# ShoulderDriver.net
KiCad netlist of a schematic drawn in Altium Designer
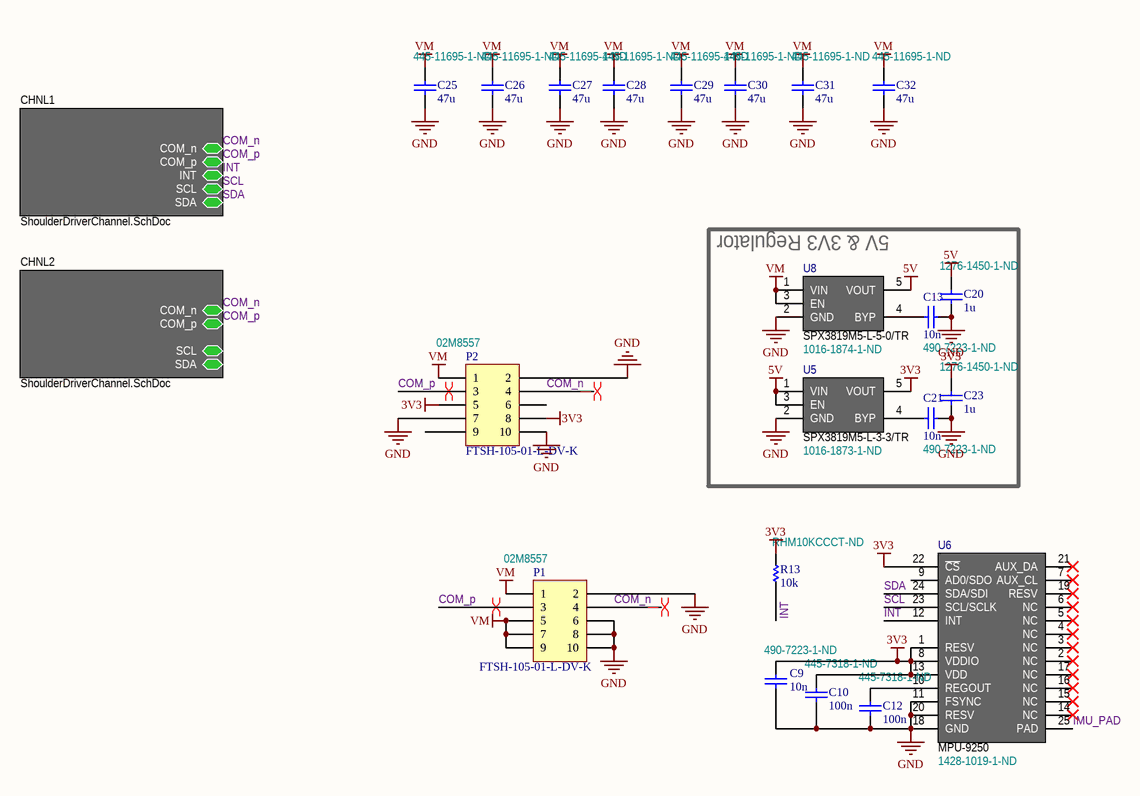
[diagram p0: ShoulderDriver.SchDoc]

(export (version "E")
  (design (tool "Eeschema 10.0.6"))
  (components
    (comp (ref "C9")
      (value "10n")
      (footprint "CAPC0603N")
      (description "Capacitor (Semiconductor SIM Model)")
      (fields
        (field (name "SUPPLIER PART NUMBER 1") "490-7223-1-ND")
        (field (name "PUBLISHER") "Altium Limited")
      )
      (libsource (lib "Miscellaneous Devices") (part "Cap Semi"))
    )
    (comp (ref "C10")
      (value "100n")
      (footprint "CAPC0603N")
      (description "Capacitor (Semiconductor SIM Model)")
      (fields
        (field (name "SUPPLIER PART NUMBER 1") "445-7318-1-ND")
        (field (name "PUBLISHER") "Altium Limited")
      )
      (libsource (lib "Miscellaneous Devices") (part "Cap Semi"))
    )
    (comp (ref "C12")
      (value "100n")
      (footprint "CAPC0603N")
      (description "Capacitor (Semiconductor SIM Model)")
      (fields
        (field (name "SUPPLIER PART NUMBER 1") "445-7318-1-ND")
        (field (name "PUBLISHER") "Altium Limited")
      )
      (libsource (lib "Miscellaneous Devices") (part "Cap Semi"))
    )
    (comp (ref "C13")
      (value "10n")
      (footprint "CAPC0603N")
      (description "Capacitor (Semiconductor SIM Model)")
      (fields
        (field (name "SUPPLIER PART NUMBER 1") "490-7223-1-ND")
        (field (name "PUBLISHER") "Altium Limited")
      )
      (libsource (lib "Miscellaneous Devices") (part "Cap Semi"))
    )
    (comp (ref "C20")
      (value "1u")
      (footprint "CAPC1005N")
      (description "Capacitor (Semiconductor SIM Model)")
      (fields
        (field (name "SUPPLIER PART NUMBER 1") "1276-1450-1-ND")
        (field (name "PUBLISHER") "Altium Limited")
      )
      (libsource (lib "Miscellaneous Devices") (part "Cap Semi"))
    )
    (comp (ref "C21")
      (value "10n")
      (footprint "CAPC0603N")
      (description "Capacitor (Semiconductor SIM Model)")
      (fields
        (field (name "SUPPLIER PART NUMBER 1") "490-7223-1-ND")
        (field (name "PUBLISHER") "Altium Limited")
      )
      (libsource (lib "Miscellaneous Devices") (part "Cap Semi"))
    )
    (comp (ref "C23")
      (value "1u")
      (footprint "CAPC1005N")
      (description "Capacitor (Semiconductor SIM Model)")
      (fields
        (field (name "SUPPLIER PART NUMBER 1") "1276-1450-1-ND")
        (field (name "PUBLISHER") "Altium Limited")
      )
      (libsource (lib "Miscellaneous Devices") (part "Cap Semi"))
    )
    (comp (ref "C25")
      (value "47u")
      (footprint "CAPC3216N")
      (description "Capacitor (Semiconductor SIM Model)")
      (fields
        (field (name "SUPPLIER PART NUMBER 1") "445-11695-1-ND")
        (field (name "PUBLISHER") "Altium Limited")
      )
      (libsource (lib "Miscellaneous Devices") (part "Cap Semi"))
    )
    (comp (ref "C26")
      (value "47u")
      (footprint "CAPC3216N")
      (description "Capacitor (Semiconductor SIM Model)")
      (fields
        (field (name "SUPPLIER PART NUMBER 1") "445-11695-1-ND")
        (field (name "PUBLISHER") "Altium Limited")
      )
      (libsource (lib "Miscellaneous Devices") (part "Cap Semi"))
    )
    (comp (ref "C27")
      (value "47u")
      (footprint "CAPC3216N")
      (description "Capacitor (Semiconductor SIM Model)")
      (fields
        (field (name "SUPPLIER PART NUMBER 1") "445-11695-1-ND")
        (field (name "PUBLISHER") "Altium Limited")
      )
      (libsource (lib "Miscellaneous Devices") (part "Cap Semi"))
    )
    (comp (ref "C28")
      (value "47u")
      (footprint "CAPC3216N")
      (description "Capacitor (Semiconductor SIM Model)")
      (fields
        (field (name "SUPPLIER PART NUMBER 1") "445-11695-1-ND")
        (field (name "PUBLISHER") "Altium Limited")
      )
      (libsource (lib "Miscellaneous Devices") (part "Cap Semi"))
    )
    (comp (ref "C29")
      (value "47u")
      (footprint "CAPC3216N")
      (description "Capacitor (Semiconductor SIM Model)")
      (fields
        (field (name "SUPPLIER PART NUMBER 1") "445-11695-1-ND")
        (field (name "PUBLISHER") "Altium Limited")
      )
      (libsource (lib "Miscellaneous Devices") (part "Cap Semi"))
    )
    (comp (ref "C30")
      (value "47u")
      (footprint "CAPC3216N")
      (description "Capacitor (Semiconductor SIM Model)")
      (fields
        (field (name "SUPPLIER PART NUMBER 1") "445-11695-1-ND")
        (field (name "PUBLISHER") "Altium Limited")
      )
      (libsource (lib "Miscellaneous Devices") (part "Cap Semi"))
    )
    (comp (ref "C31")
      (value "47u")
      (footprint "CAPC3216N")
      (description "Capacitor (Semiconductor SIM Model)")
      (fields
        (field (name "SUPPLIER PART NUMBER 1") "445-11695-1-ND")
        (field (name "PUBLISHER") "Altium Limited")
      )
      (libsource (lib "Miscellaneous Devices") (part "Cap Semi"))
    )
    (comp (ref "C32")
      (value "47u")
      (footprint "CAPC3216N")
      (description "Capacitor (Semiconductor SIM Model)")
      (fields
        (field (name "SUPPLIER PART NUMBER 1") "445-11695-1-ND")
        (field (name "PUBLISHER") "Altium Limited")
      )
      (libsource (lib "Miscellaneous Devices") (part "Cap Semi"))
    )
    (comp (ref "P1")
      (value "FTSH-105-01-L-DV-K")
      (footprint "FTSH-105-01-L-DV-K")
      (description "Header, 5-Pin, Dual row")
      (fields (field (name "SUPPLIER PART NUMBER 1") "02M8557") (field (name "PUBLISHER") "Altium Limited"))
      (libsource (lib "Miscellaneous Connectors") (part "MHDR2X5"))
    )
    (comp (ref "P2")
      (value "FTSH-105-01-L-DV-K")
      (footprint "FTSH-105-01-L-DV-K")
      (description "Header, 5-Pin, Dual row")
      (fields (field (name "SUPPLIER PART NUMBER 1") "02M8557") (field (name "PUBLISHER") "Altium Limited"))
      (libsource (lib "Miscellaneous Connectors") (part "MHDR2X5"))
    )
    (comp (ref "R13")
      (value "10k")
      (footprint "RESC0603N")
      (description "Semiconductor Resistor")
      (fields
        (field (name "SUPPLIER PART NUMBER 1") "RHM10KCCCT-ND")
        (field (name "PUBLISHER") "Altium Limited")
      )
      (libsource (lib "Miscellaneous Devices") (part "Res Semi"))
    )
    (comp (ref "U5")
      (value "SPX3819M5-L-3-3/TR")
      (footprint "SOT23-5AN")
      (description "IC REG LDO 3.3V 0.5A SOT23-5")
      (fields
        (field (name "MANUFACTURER") "Exar Corporation")
        (field (name "SUPPLIER PART NUMBER 1") "1016-1873-1-ND")
      )
      (libsource (lib "Exar LDO Regulator") (part "SPX3819M5-L-3-3/TR"))
    )
    (comp (ref "U6")
      (value "MPU-9250")
      (footprint "QFN40P300X300X105_HS-25N")
      (description "GYRO/ACCEL/COMPASS/9-AXIS")
      (fields
        (field (name "MANUFACTURER") "InvenSense")
        (field (name "SUPPLIER PART NUMBER 1") "1428-1019-1-ND")
      )
      (libsource (lib "Invensense MPU") (part "MPU-9250"))
    )
    (comp (ref "U8")
      (value "SPX3819M5-L-5-0/TR")
      (footprint "SOT23-5AN")
      (description "IC REG LDO 5V 0.5A SOT23-5")
      (fields
        (field (name "MANUFACTURER") "Exar Corporation")
        (field (name "SUPPLIER PART NUMBER 1") "1016-1874-1-ND")
      )
      (libsource (lib "Exar LDO Regulator") (part "SPX3819M5-L-5-0/TR"))
    )
  )
  (nets
    (net (code "1") (name "/COM_n") (class "Default")
      (node (ref "P1") (pin "4") (pinfunction "4_4") (pintype "passive"))
      (node (ref "P2") (pin "4") (pinfunction "4_4") (pintype "passive"))
    )
    (net (code "2") (name "/COM_p") (class "Default")
      (node (ref "P1") (pin "3") (pinfunction "3_3") (pintype "passive"))
      (node (ref "P2") (pin "3") (pinfunction "3_3") (pintype "passive"))
    )
    (net (code "3") (name "/IMU_PAD") (class "Default")
      (node (ref "U6") (pin "25") (pinfunction "PAD_25") (pintype "power_in"))
    )
    (net (code "4") (name "/INT") (class "Default")
      (node (ref "R13") (pin "1") (pinfunction "1_1") (pintype "passive"))
      (node (ref "U6") (pin "12") (pinfunction "INT_12") (pintype "power_in"))
    )
    (net (code "5") (name "/SCL") (class "Default")
      (node (ref "U6") (pin "23") (pinfunction "SCL/SCLK_23") (pintype "power_in"))
    )
    (net (code "7") (name "/SDA") (class "Default")
      (node (ref "U6") (pin "24") (pinfunction "SDA/SDI_24") (pintype "power_in"))
    )
    (net (code "9") (name "3V3") (class "Default")
      (node (ref "C10") (pin "2") (pinfunction "2_2") (pintype "passive"))
      (node (ref "C23") (pin "2") (pinfunction "2_2") (pintype "passive"))
      (node (ref "C9") (pin "2") (pinfunction "2_2") (pintype "passive"))
      (node (ref "P2") (pin "5") (pinfunction "5_5") (pintype "passive"))
      (node (ref "P2") (pin "8") (pinfunction "8_8") (pintype "passive"))
      (node (ref "R13") (pin "2") (pinfunction "2_2") (pintype "passive"))
      (node (ref "U5") (pin "5") (pinfunction "VOUT_5") (pintype "power_in"))
      (node (ref "U6") (pin "1") (pinfunction "RESV_1") (pintype "power_in"))
      (node (ref "U6") (pin "13") (pinfunction "VDD_13") (pintype "power_in"))
      (node (ref "U6") (pin "22") (pinfunction "~{CS}_22") (pintype "power_in"))
      (node (ref "U6") (pin "8") (pinfunction "VDDIO_8") (pintype "power_in"))
    )
    (net (code "10") (name "5V") (class "Default")
      (node (ref "C20") (pin "2") (pinfunction "2_2") (pintype "passive"))
      (node (ref "U5") (pin "1") (pinfunction "VIN_1") (pintype "power_in"))
      (node (ref "U5") (pin "3") (pinfunction "EN_3") (pintype "power_in"))
      (node (ref "U8") (pin "5") (pinfunction "VOUT_5") (pintype "power_in"))
    )
    (net (code "11") (name "GND") (class "Default")
      (node (ref "C10") (pin "1") (pinfunction "1_1") (pintype "passive"))
      (node (ref "C12") (pin "1") (pinfunction "1_1") (pintype "passive"))
      (node (ref "C13") (pin "1") (pinfunction "1_1") (pintype "passive"))
      (node (ref "C20") (pin "1") (pinfunction "1_1") (pintype "passive"))
      (node (ref "C21") (pin "1") (pinfunction "1_1") (pintype "passive"))
      (node (ref "C23") (pin "1") (pinfunction "1_1") (pintype "passive"))
      (node (ref "C25") (pin "1") (pinfunction "1_1") (pintype "passive"))
      (node (ref "C26") (pin "1") (pinfunction "1_1") (pintype "passive"))
      (node (ref "C27") (pin "1") (pinfunction "1_1") (pintype "passive"))
      (node (ref "C28") (pin "1") (pinfunction "1_1") (pintype "passive"))
      (node (ref "C29") (pin "1") (pinfunction "1_1") (pintype "passive"))
      (node (ref "C30") (pin "1") (pinfunction "1_1") (pintype "passive"))
      (node (ref "C31") (pin "1") (pinfunction "1_1") (pintype "passive"))
      (node (ref "C32") (pin "1") (pinfunction "1_1") (pintype "passive"))
      (node (ref "C9") (pin "1") (pinfunction "1_1") (pintype "passive"))
      (node (ref "P1") (pin "10") (pinfunction "10_10") (pintype "passive"))
      (node (ref "P1") (pin "2") (pinfunction "2_2") (pintype "passive"))
      (node (ref "P1") (pin "6") (pinfunction "6_6") (pintype "passive"))
      (node (ref "P1") (pin "8") (pinfunction "8_8") (pintype "passive"))
      (node (ref "P2") (pin "10") (pinfunction "10_10") (pintype "passive"))
      (node (ref "P2") (pin "2") (pinfunction "2_2") (pintype "passive"))
      (node (ref "P2") (pin "7") (pinfunction "7_7") (pintype "passive"))
      (node (ref "U5") (pin "2") (pinfunction "GND_2") (pintype "power_in"))
      (node (ref "U6") (pin "11") (pinfunction "FSYNC_11") (pintype "power_in"))
      (node (ref "U6") (pin "18") (pinfunction "GND_18") (pintype "power_in"))
      (node (ref "U6") (pin "20") (pinfunction "RESV_20") (pintype "power_in"))
      (node (ref "U8") (pin "2") (pinfunction "GND_2") (pintype "power_in"))
    )
    (net (code "12") (name "Net-(U5-BYP)") (class "Default")
      (node (ref "C21") (pin "2") (pinfunction "2_2") (pintype "passive"))
      (node (ref "U5") (pin "4") (pinfunction "BYP_4") (pintype "power_in"))
    )
    (net (code "13") (name "Net-(U6-REGOUT)") (class "Default")
      (node (ref "C12") (pin "2") (pinfunction "2_2") (pintype "passive"))
      (node (ref "U6") (pin "10") (pinfunction "REGOUT_10") (pintype "power_in"))
    )
    (net (code "14") (name "Net-(U8-BYP)") (class "Default")
      (node (ref "C13") (pin "2") (pinfunction "2_2") (pintype "passive"))
      (node (ref "U8") (pin "4") (pinfunction "BYP_4") (pintype "power_in"))
    )
    (net (code "15") (name "VM") (class "Default")
      (node (ref "C25") (pin "2") (pinfunction "2_2") (pintype "passive"))
      (node (ref "C26") (pin "2") (pinfunction "2_2") (pintype "passive"))
      (node (ref "C27") (pin "2") (pinfunction "2_2") (pintype "passive"))
      (node (ref "C28") (pin "2") (pinfunction "2_2") (pintype "passive"))
      (node (ref "C29") (pin "2") (pinfunction "2_2") (pintype "passive"))
      (node (ref "C30") (pin "2") (pinfunction "2_2") (pintype "passive"))
      (node (ref "C31") (pin "2") (pinfunction "2_2") (pintype "passive"))
      (node (ref "C32") (pin "2") (pinfunction "2_2") (pintype "passive"))
      (node (ref "P1") (pin "1") (pinfunction "1_1") (pintype "passive"))
      (node (ref "P1") (pin "5") (pinfunction "5_5") (pintype "passive"))
      (node (ref "P1") (pin "7") (pinfunction "7_7") (pintype "passive"))
      (node (ref "P1") (pin "9") (pinfunction "9_9") (pintype "passive"))
      (node (ref "P2") (pin "1") (pinfunction "1_1") (pintype "passive"))
      (node (ref "U8") (pin "1") (pinfunction "VIN_1") (pintype "power_in"))
      (node (ref "U8") (pin "3") (pinfunction "EN_3") (pintype "power_in"))
    )
    (net (code "16") (name "unconnected-(P2-Pad6)") (class "Default")
      (node (ref "P2") (pin "6") (pinfunction "6_6") (pintype "passive"))
    )
    (net (code "17") (name "unconnected-(P2-Pad9)") (class "Default")
      (node (ref "P2") (pin "9") (pinfunction "9_9") (pintype "passive"))
    )
    (net (code "18") (name "unconnected-(U6-AD0{slash}SDO-Pad9)") (class "Default")
      (node (ref "U6") (pin "9") (pinfunction "AD0/SDO_9") (pintype "power_in"))
    )
    (net (code "19") (name "unconnected-(U6-AUX_CL-Pad7)") (class "Default")
      (node (ref "U6") (pin "7") (pinfunction "AUX_CL_7") (pintype "power_in+no_connect"))
    )
    (net (code "20") (name "unconnected-(U6-AUX_DA-Pad21)") (class "Default")
      (node (ref "U6") (pin "21") (pinfunction "AUX_DA_21") (pintype "power_in+no_connect"))
    )
    (net (code "21") (name "unconnected-(U6-NC-Pad2)") (class "Default")
      (node (ref "U6") (pin "2") (pinfunction "NC_2") (pintype "power_in+no_connect"))
    )
    (net (code "22") (name "unconnected-(U6-NC-Pad3)") (class "Default")
      (node (ref "U6") (pin "3") (pinfunction "NC_3") (pintype "power_in+no_connect"))
    )
    (net (code "23") (name "unconnected-(U6-NC-Pad4)") (class "Default")
      (node (ref "U6") (pin "4") (pinfunction "NC_4") (pintype "power_in+no_connect"))
    )
    (net (code "24") (name "unconnected-(U6-NC-Pad5)") (class "Default")
      (node (ref "U6") (pin "5") (pinfunction "NC_5") (pintype "power_in+no_connect"))
    )
    (net (code "25") (name "unconnected-(U6-NC-Pad6)") (class "Default")
      (node (ref "U6") (pin "6") (pinfunction "NC_6") (pintype "power_in+no_connect"))
    )
    (net (code "26") (name "unconnected-(U6-NC-Pad14)") (class "Default")
      (node (ref "U6") (pin "14") (pinfunction "NC_14") (pintype "power_in+no_connect"))
    )
    (net (code "27") (name "unconnected-(U6-NC-Pad15)") (class "Default")
      (node (ref "U6") (pin "15") (pinfunction "NC_15") (pintype "power_in+no_connect"))
    )
    (net (code "28") (name "unconnected-(U6-NC-Pad16)") (class "Default")
      (node (ref "U6") (pin "16") (pinfunction "NC_16") (pintype "power_in+no_connect"))
    )
    (net (code "29") (name "unconnected-(U6-NC-Pad17)") (class "Default")
      (node (ref "U6") (pin "17") (pinfunction "NC_17") (pintype "power_in+no_connect"))
    )
    (net (code "30") (name "unconnected-(U6-RESV-Pad19)") (class "Default")
      (node (ref "U6") (pin "19") (pinfunction "RESV_19") (pintype "power_in+no_connect"))
    )
  )
)
